# sd-card.net
KiCad netlist of a schematic drawn in Altium Designer
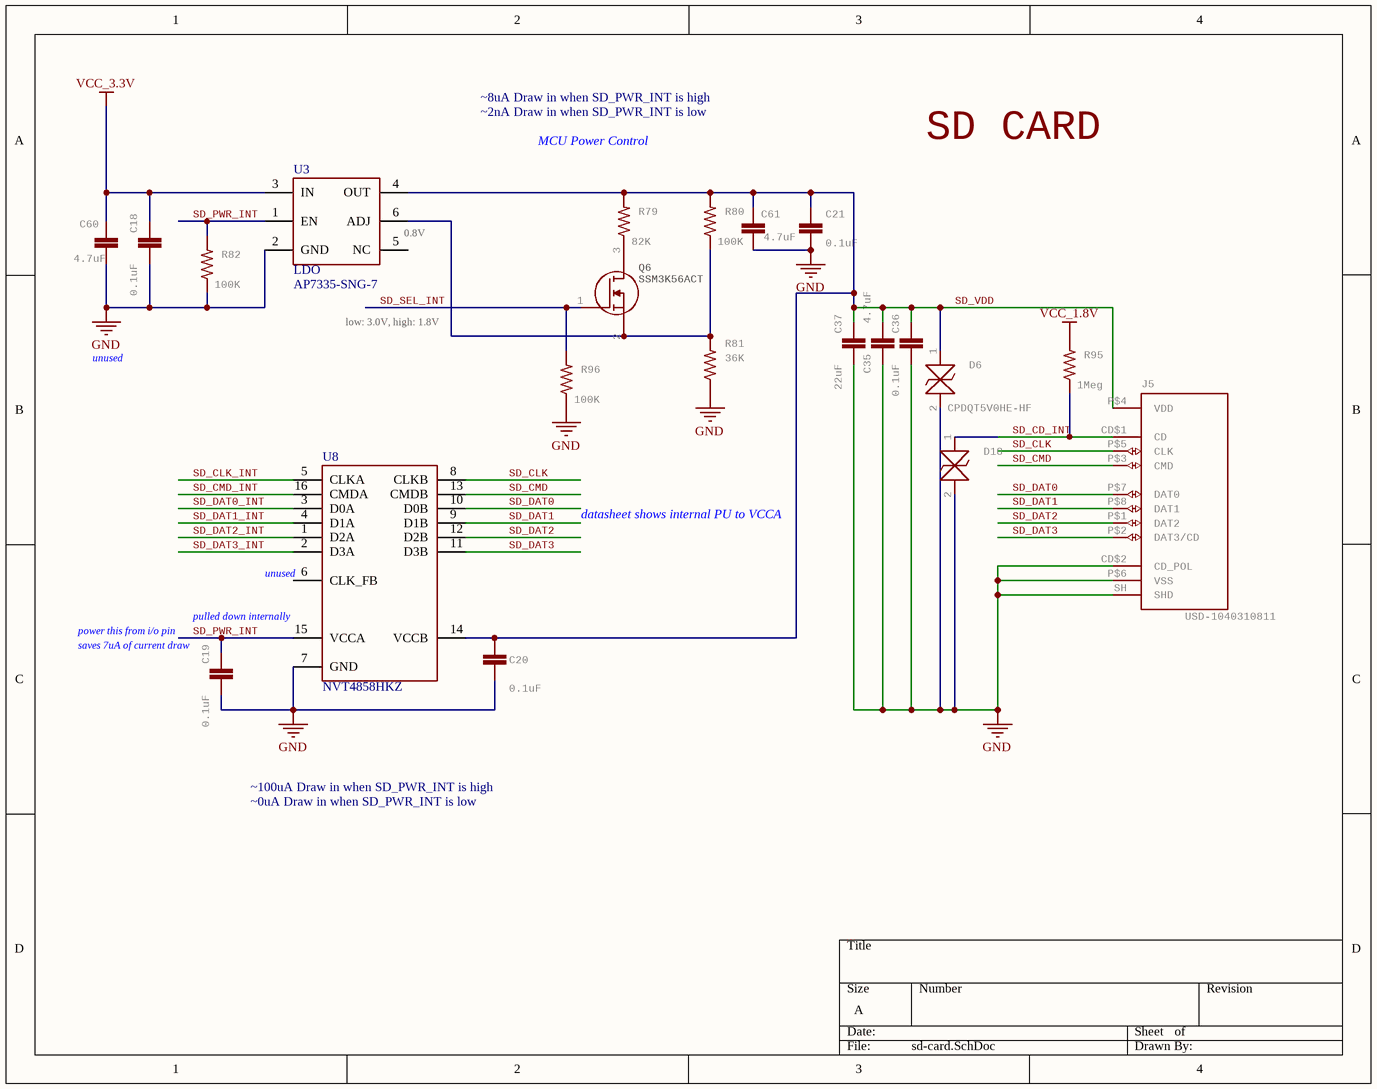
[diagram p0: sd-card.SchDoc]

(export (version "E")
  (design (tool "Eeschema 10.0.6"))
  (components
    (comp (ref "C18")
      (value "0.1uF")
      (footprint "0402-CAP")
      (description "CAPACITOR, European symbol")
      (fields (field (name "MPN") "C0402C104Z4VAC"))
      (libsource (lib "openmv-ae3") (part "C-EUC0201"))
    )
    (comp (ref "C19")
      (value "0.1uF")
      (footprint "0402-CAP")
      (description "CAPACITOR, European symbol")
      (fields (field (name "MPN") "C0402C104Z4VAC"))
      (libsource (lib "openmv-ae3") (part "C-EUC0201"))
    )
    (comp (ref "C20")
      (value "0.1uF")
      (footprint "0402-CAP")
      (description "CAPACITOR, European symbol")
      (fields (field (name "MPN") "C0402C104Z4VAC"))
      (libsource (lib "openmv-ae3") (part "C-EUC0201"))
    )
    (comp (ref "C21")
      (value "0.1uF")
      (footprint "0402-CAP")
      (description "CAPACITOR, European symbol")
      (fields (field (name "MPN") "C0402C104Z4VAC"))
      (libsource (lib "openmv-ae3") (part "C-EUC0201"))
    )
    (comp (ref "C35")
      (value "4.7uF")
      (footprint "0402-CAP")
      (description "CapacitorStandard 0603 ceramic capacitor, and 0.1\" leaded capacitor.")
      (fields (field (name "MPN") "JMK105BBJ475MV-F") (field (name "LIBRARYNAME") "sfe"))
      (libsource (lib "") (part "CAP0402-CAP_1"))
    )
    (comp (ref "C36")
      (value "0.1uF")
      (footprint "0402-CAP")
      (description "CAPACITOR, European symbol")
      (fields (field (name "MPN") "C0402C104Z4VAC"))
      (libsource (lib "openmv-ae3") (part "C-EUC0201"))
    )
    (comp (ref "C37")
      (value "22uF")
      (footprint "0805")
      (fields (field (name "MPN") "CL21A226MQQNNNE"))
      (libsource (lib "openmv-ae3") (part "22UF-0805-6.3V-20%"))
    )
    (comp (ref "C60")
      (value "4.7uF")
      (footprint "0402-CAP")
      (description "CapacitorStandard 0603 ceramic capacitor, and 0.1\" leaded capacitor.")
      (fields (field (name "MPN") "JMK105BBJ475MV-F") (field (name "LIBRARYNAME") "sfe"))
      (libsource (lib "openmv-ae3") (part "CAP0402-CAP"))
    )
    (comp (ref "C61")
      (value "4.7uF")
      (footprint "0402-CAP")
      (description "CapacitorStandard 0603 ceramic capacitor, and 0.1\" leaded capacitor.")
      (fields (field (name "MPN") "JMK105BBJ475MV-F") (field (name "LIBRARYNAME") "sfe"))
      (libsource (lib "openmv-ae3") (part "CAP0402-CAP"))
    )
    (comp (ref "D6")
      (value "CPDQT5V0HE-HF")
      (footprint "CPDQT5V0HEHF")
      (description "ESD Suppressors / TVS Diodes DIODE ESD 5VWM 65W 0402/SOD-923F   Source:  Datasheet")
      (fields (field (name "MOUSER_PART_NUMBER") "MOUSER_PART_NUMBER"))
      (libsource (lib "openmv-ae3") (part "CPDQT5V0HE-HF"))
    )
    (comp (ref "D18")
      (value "CPDQT5V0HE-HF")
      (footprint "CPDQT5V0HEHF")
      (description "ESD Suppressors / TVS Diodes DIODE ESD 5VWM 65W 0402/SOD-923F   Source:  Datasheet")
      (fields (field (name "MOUSER_PART_NUMBER") "MOUSER_PART_NUMBER"))
      (libsource (lib "openmv-ae3") (part "CPDQT5V0HE-HF"))
    )
    (comp (ref "J5")
      (value "USD-1040310811")
      (footprint "1040310811")
      (description "uSD Slot")
      (fields (field (name "MPN") "104031-0811"))
      (libsource (lib "openmv-ae3") (part "USD-1040310811"))
    )
    (comp (ref "Q6")
      (value "NMOS")
      (footprint "DFN1006")
      (fields (field (name "MF") "Toshiba") (field (name "MPN") "SSM3K56ACT"))
      (libsource (lib "openmv-ae3") (part "NMOS"))
    )
    (comp (ref "R79")
      (value "82K")
      (footprint "0402-RES")
      (description "ResistorBasic schematic elements and footprints for 0603, 1206, and PTH resistors.")
      (fields (field (name "LIBRARYNAME") "sfe"))
      (libsource (lib "openmv-ae3") (part "RESISTOR0402-RES"))
    )
    (comp (ref "R80")
      (value "100K")
      (footprint "0402-RES")
      (description "ResistorBasic schematic elements and footprints for 0603, 1206, and PTH resistors.")
      (fields (field (name "MPN") "AC0402FR-07100KL") (field (name "LIBRARYNAME") "sfe"))
      (libsource (lib "openmv-ae3") (part "RESISTOR0402-RES"))
    )
    (comp (ref "R81")
      (value "36K")
      (footprint "0402-RES")
      (description "ResistorBasic schematic elements and footprints for 0603, 1206, and PTH resistors.")
      (fields (field (name "LIBRARYNAME") "sfe"))
      (libsource (lib "openmv-ae3") (part "RESISTOR0402-RES"))
    )
    (comp (ref "R82")
      (value "100K")
      (footprint "0402-RES")
      (description "ResistorBasic schematic elements and footprints for 0603, 1206, and PTH resistors.")
      (fields (field (name "MPN") "AC0402FR-07100KL") (field (name "LIBRARYNAME") "sfe"))
      (libsource (lib "openmv-ae3") (part "RESISTOR0402-RES"))
    )
    (comp (ref "R95")
      (value "1Meg")
      (footprint "R0201")
      (fields (field (name "LIBRARYNAME") "sfe"))
      (libsource (lib "openmv-ae3") (part "RESISTOR0402-RES"))
    )
    (comp (ref "R96")
      (value "100K")
      (footprint "R0201")
      (description "ResistorBasic schematic elements and footprints for 0603, 1206, and PTH resistors.")
      (fields (field (name "LIBRARYNAME") "sfe"))
      (libsource (lib "openmv-ae3") (part "RESISTOR0402-RES"))
    )
    (comp (ref "U3")
      (value "LDO")
      (footprint "DFN2020-6")
      (fields (field (name "MPN") "AP7335-SNG-7") (field (name "MF") "Diodes Inc"))
      (libsource (lib "openmv-ae3") (part "AP7335-SNG-7"))
    )
    (comp (ref "U8")
      (value "NVT4858HKZ")
      (footprint "NVT4858HKZ")
      (fields (field (name "MF") "NXP"))
      (libsource (lib "openmv-ae3") (part "NVT4858HKZ"))
    )
  )
  (nets
    (net (code "1") (name "/SD_CD_INT") (class "Default")
      (node (ref "D18") (pin "1") (pinfunction "1_1") (pintype "bidirectional"))
      (node (ref "J5") (pin "CD$1") (pinfunction "CD_CD$1") (pintype "power_in"))
      (node (ref "R95") (pin "1") (pinfunction "1_1") (pintype "passive"))
    )
    (net (code "2") (name "/SD_CLK") (class "Default")
      (node (ref "J5") (pin "P$5") (pinfunction "CLK_P$5") (pintype "bidirectional"))
      (node (ref "U8") (pin "8") (pinfunction "CLKB_8") (pintype "passive"))
    )
    (net (code "3") (name "/SD_CLK_INT") (class "Default")
      (node (ref "U8") (pin "5") (pinfunction "CLKA_5") (pintype "passive"))
    )
    (net (code "4") (name "/SD_CMD") (class "Default")
      (node (ref "J5") (pin "P$3") (pinfunction "CMD_P$3") (pintype "bidirectional"))
      (node (ref "U8") (pin "13") (pinfunction "CMDB_13") (pintype "passive"))
    )
    (net (code "5") (name "/SD_CMD_INT") (class "Default")
      (node (ref "U8") (pin "16") (pinfunction "CMDA_16") (pintype "passive"))
    )
    (net (code "6") (name "/SD_DAT0") (class "Default")
      (node (ref "J5") (pin "P$7") (pinfunction "DAT0_P$7") (pintype "bidirectional"))
      (node (ref "U8") (pin "10") (pinfunction "D0B_10") (pintype "passive"))
    )
    (net (code "7") (name "/SD_DAT0_INT") (class "Default")
      (node (ref "U8") (pin "3") (pinfunction "D0A_3") (pintype "passive"))
    )
    (net (code "8") (name "/SD_DAT1") (class "Default")
      (node (ref "J5") (pin "P$8") (pinfunction "DAT1_P$8") (pintype "bidirectional"))
      (node (ref "U8") (pin "9") (pinfunction "D1B_9") (pintype "passive"))
    )
    (net (code "9") (name "/SD_DAT1_INT") (class "Default")
      (node (ref "U8") (pin "4") (pinfunction "D1A_4") (pintype "passive"))
    )
    (net (code "10") (name "/SD_DAT2") (class "Default")
      (node (ref "J5") (pin "P$1") (pinfunction "DAT2_P$1") (pintype "bidirectional"))
      (node (ref "U8") (pin "12") (pinfunction "D2B_12") (pintype "passive"))
    )
    (net (code "11") (name "/SD_DAT2_INT") (class "Default")
      (node (ref "U8") (pin "1") (pinfunction "D2A_1") (pintype "passive"))
    )
    (net (code "12") (name "/SD_DAT3") (class "Default")
      (node (ref "J5") (pin "P$2") (pinfunction "DAT3/CD_P$2") (pintype "bidirectional"))
      (node (ref "U8") (pin "11") (pinfunction "D3B_11") (pintype "passive"))
    )
    (net (code "13") (name "/SD_DAT3_INT") (class "Default")
      (node (ref "U8") (pin "2") (pinfunction "D3A_2") (pintype "passive"))
    )
    (net (code "14") (name "/SD_PWR_INT") (class "Default")
      (node (ref "C19") (pin "1") (pinfunction "1_1") (pintype "passive"))
      (node (ref "R82") (pin "2") (pinfunction "2_2") (pintype "passive"))
      (node (ref "U3") (pin "1") (pinfunction "EN_1") (pintype "passive"))
      (node (ref "U8") (pin "15") (pinfunction "VCCA_15") (pintype "passive"))
    )
    (net (code "15") (name "/SD_SEL_INT") (class "Default")
      (node (ref "Q6") (pin "1") (pinfunction "G_1") (pintype "bidirectional"))
      (node (ref "R96") (pin "2") (pinfunction "2_2") (pintype "passive"))
    )
    (net (code "16") (name "/SD_VDD") (class "Default")
      (node (ref "C20") (pin "1") (pinfunction "1_1") (pintype "passive"))
      (node (ref "C21") (pin "1") (pinfunction "1_1") (pintype "passive"))
      (node (ref "C35") (pin "2") (pinfunction "2_2") (pintype "passive"))
      (node (ref "C36") (pin "1") (pinfunction "1_1") (pintype "passive"))
      (node (ref "C37") (pin "1") (pinfunction "1_1") (pintype "passive"))
      (node (ref "C61") (pin "1") (pinfunction "1_1") (pintype "passive"))
      (node (ref "D6") (pin "1") (pinfunction "1_1") (pintype "bidirectional"))
      (node (ref "J5") (pin "P$4") (pinfunction "VDD_P$4") (pintype "power_in"))
      (node (ref "R79") (pin "2") (pinfunction "2_2") (pintype "passive"))
      (node (ref "R80") (pin "2") (pinfunction "2_2") (pintype "passive"))
      (node (ref "U3") (pin "4") (pinfunction "OUT_4") (pintype "passive"))
      (node (ref "U8") (pin "14") (pinfunction "VCCB_14") (pintype "passive"))
    )
    (net (code "17") (name "GND") (class "Default")
      (node (ref "C18") (pin "2") (pinfunction "2_2") (pintype "passive"))
      (node (ref "C19") (pin "2") (pinfunction "2_2") (pintype "passive"))
      (node (ref "C20") (pin "2") (pinfunction "2_2") (pintype "passive"))
      (node (ref "C21") (pin "2") (pinfunction "2_2") (pintype "passive"))
      (node (ref "C35") (pin "1") (pinfunction "1_1") (pintype "passive"))
      (node (ref "C36") (pin "2") (pinfunction "2_2") (pintype "passive"))
      (node (ref "C37") (pin "2") (pinfunction "2_2") (pintype "passive"))
      (node (ref "C60") (pin "2") (pinfunction "2_2") (pintype "passive"))
      (node (ref "C61") (pin "2") (pinfunction "2_2") (pintype "passive"))
      (node (ref "D18") (pin "2") (pinfunction "2_2") (pintype "bidirectional"))
      (node (ref "D6") (pin "2") (pinfunction "2_2") (pintype "bidirectional"))
      (node (ref "J5") (pin "CD$2") (pinfunction "CD_POL_CD$2") (pintype "power_in"))
      (node (ref "J5") (pin "P$6") (pinfunction "VSS_P$6") (pintype "power_in"))
      (node (ref "J5") (pin "SH") (pinfunction "SHD_SH") (pintype "power_in"))
      (node (ref "R81") (pin "1") (pinfunction "1_1") (pintype "passive"))
      (node (ref "R82") (pin "1") (pinfunction "1_1") (pintype "passive"))
      (node (ref "R96") (pin "1") (pinfunction "1_1") (pintype "passive"))
      (node (ref "U3") (pin "2") (pinfunction "GND_2") (pintype "passive"))
      (node (ref "U8") (pin "7") (pinfunction "GND_7") (pintype "passive"))
    )
    (net (code "18") (name "Net-(Q6-D)") (class "Default")
      (node (ref "Q6") (pin "3") (pinfunction "D_3") (pintype "bidirectional"))
      (node (ref "R79") (pin "1") (pinfunction "1_1") (pintype "passive"))
    )
    (net (code "19") (name "Net-(Q6-S)") (class "Default")
      (node (ref "Q6") (pin "2") (pinfunction "S_2") (pintype "bidirectional"))
      (node (ref "R80") (pin "1") (pinfunction "1_1") (pintype "passive"))
      (node (ref "R81") (pin "2") (pinfunction "2_2") (pintype "passive"))
      (node (ref "U3") (pin "6") (pinfunction "ADJ_6") (pintype "passive"))
    )
    (net (code "20") (name "VCC_1.8V") (class "Default")
      (node (ref "R95") (pin "2") (pinfunction "2_2") (pintype "passive"))
    )
    (net (code "21") (name "VCC_3.3V") (class "Default")
      (node (ref "C18") (pin "1") (pinfunction "1_1") (pintype "passive"))
      (node (ref "C60") (pin "1") (pinfunction "1_1") (pintype "passive"))
      (node (ref "U3") (pin "3") (pinfunction "IN_3") (pintype "passive"))
    )
    (net (code "22") (name "unconnected-(U3-NC-Pad5)") (class "Default")
      (node (ref "U3") (pin "5") (pinfunction "NC_5") (pintype "passive"))
    )
    (net (code "23") (name "unconnected-(U8-CLK_FB-Pad6)") (class "Default")
      (node (ref "U8") (pin "6") (pinfunction "CLK_FB_6") (pintype "passive"))
    )
  )
)
